# SCH_car_for_2024-01-24.net
KiCad netlist of a schematic drawn in EasyEDA
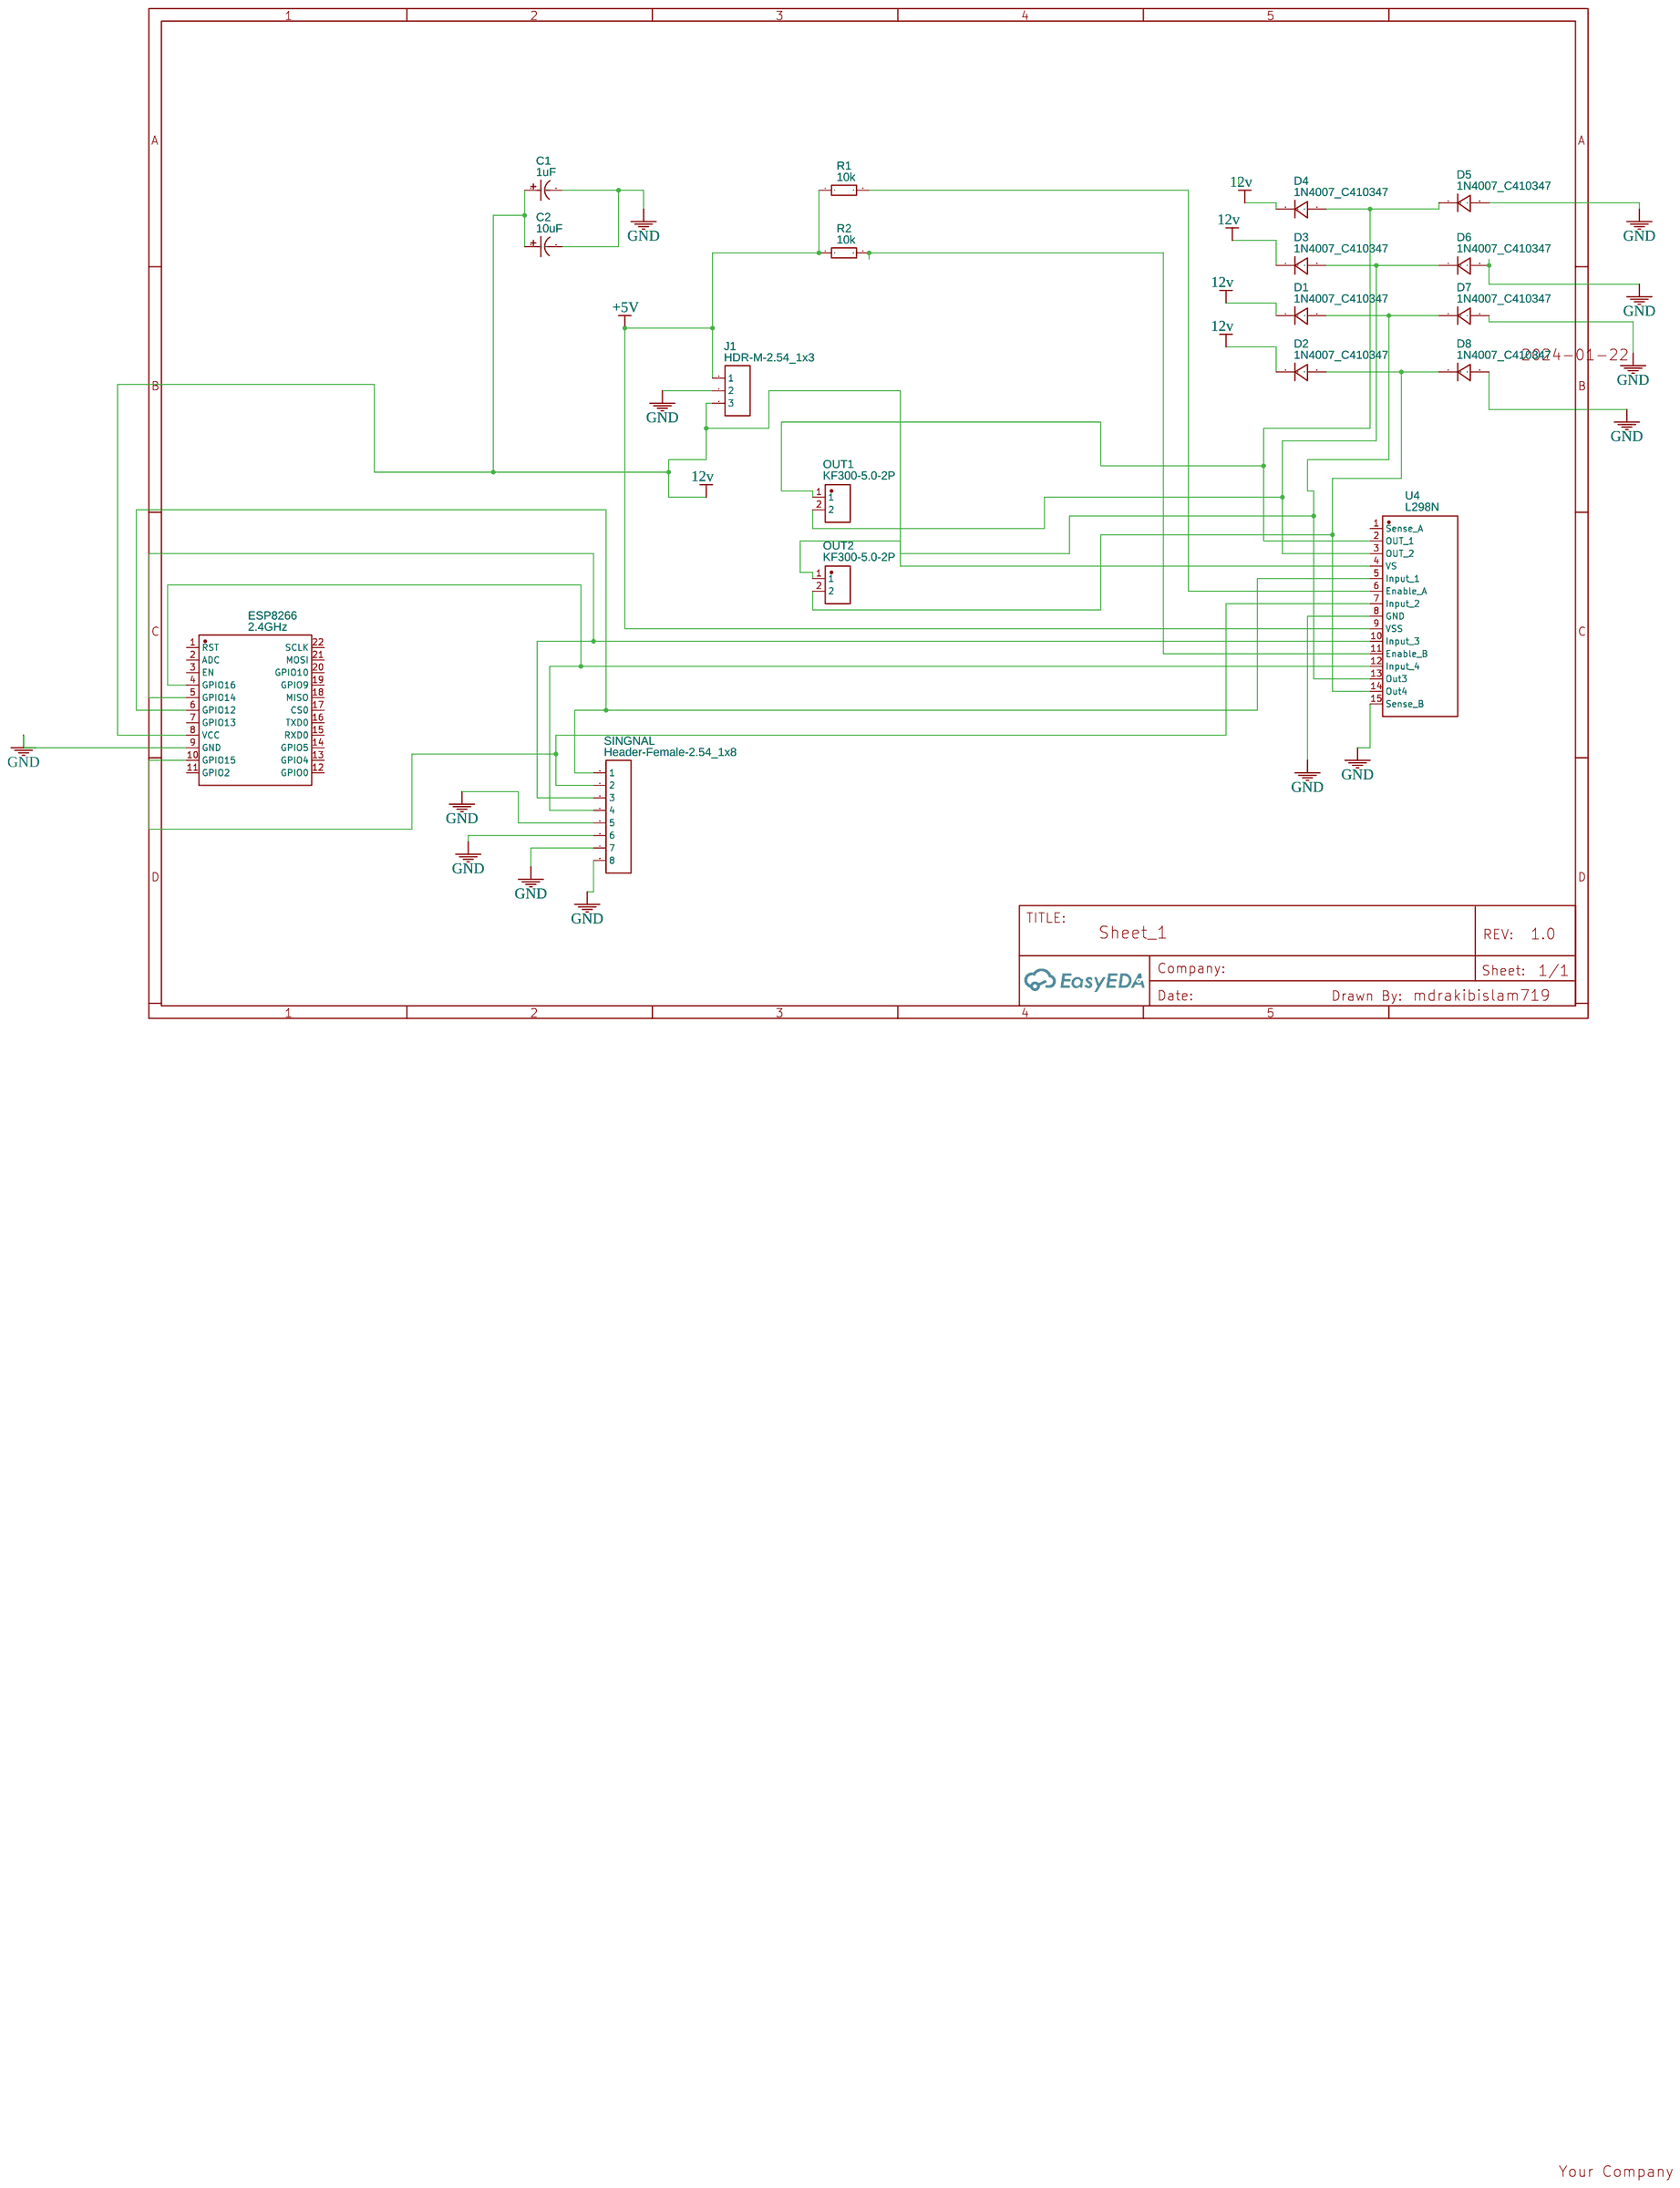
[diagram p0: Sheet_1]
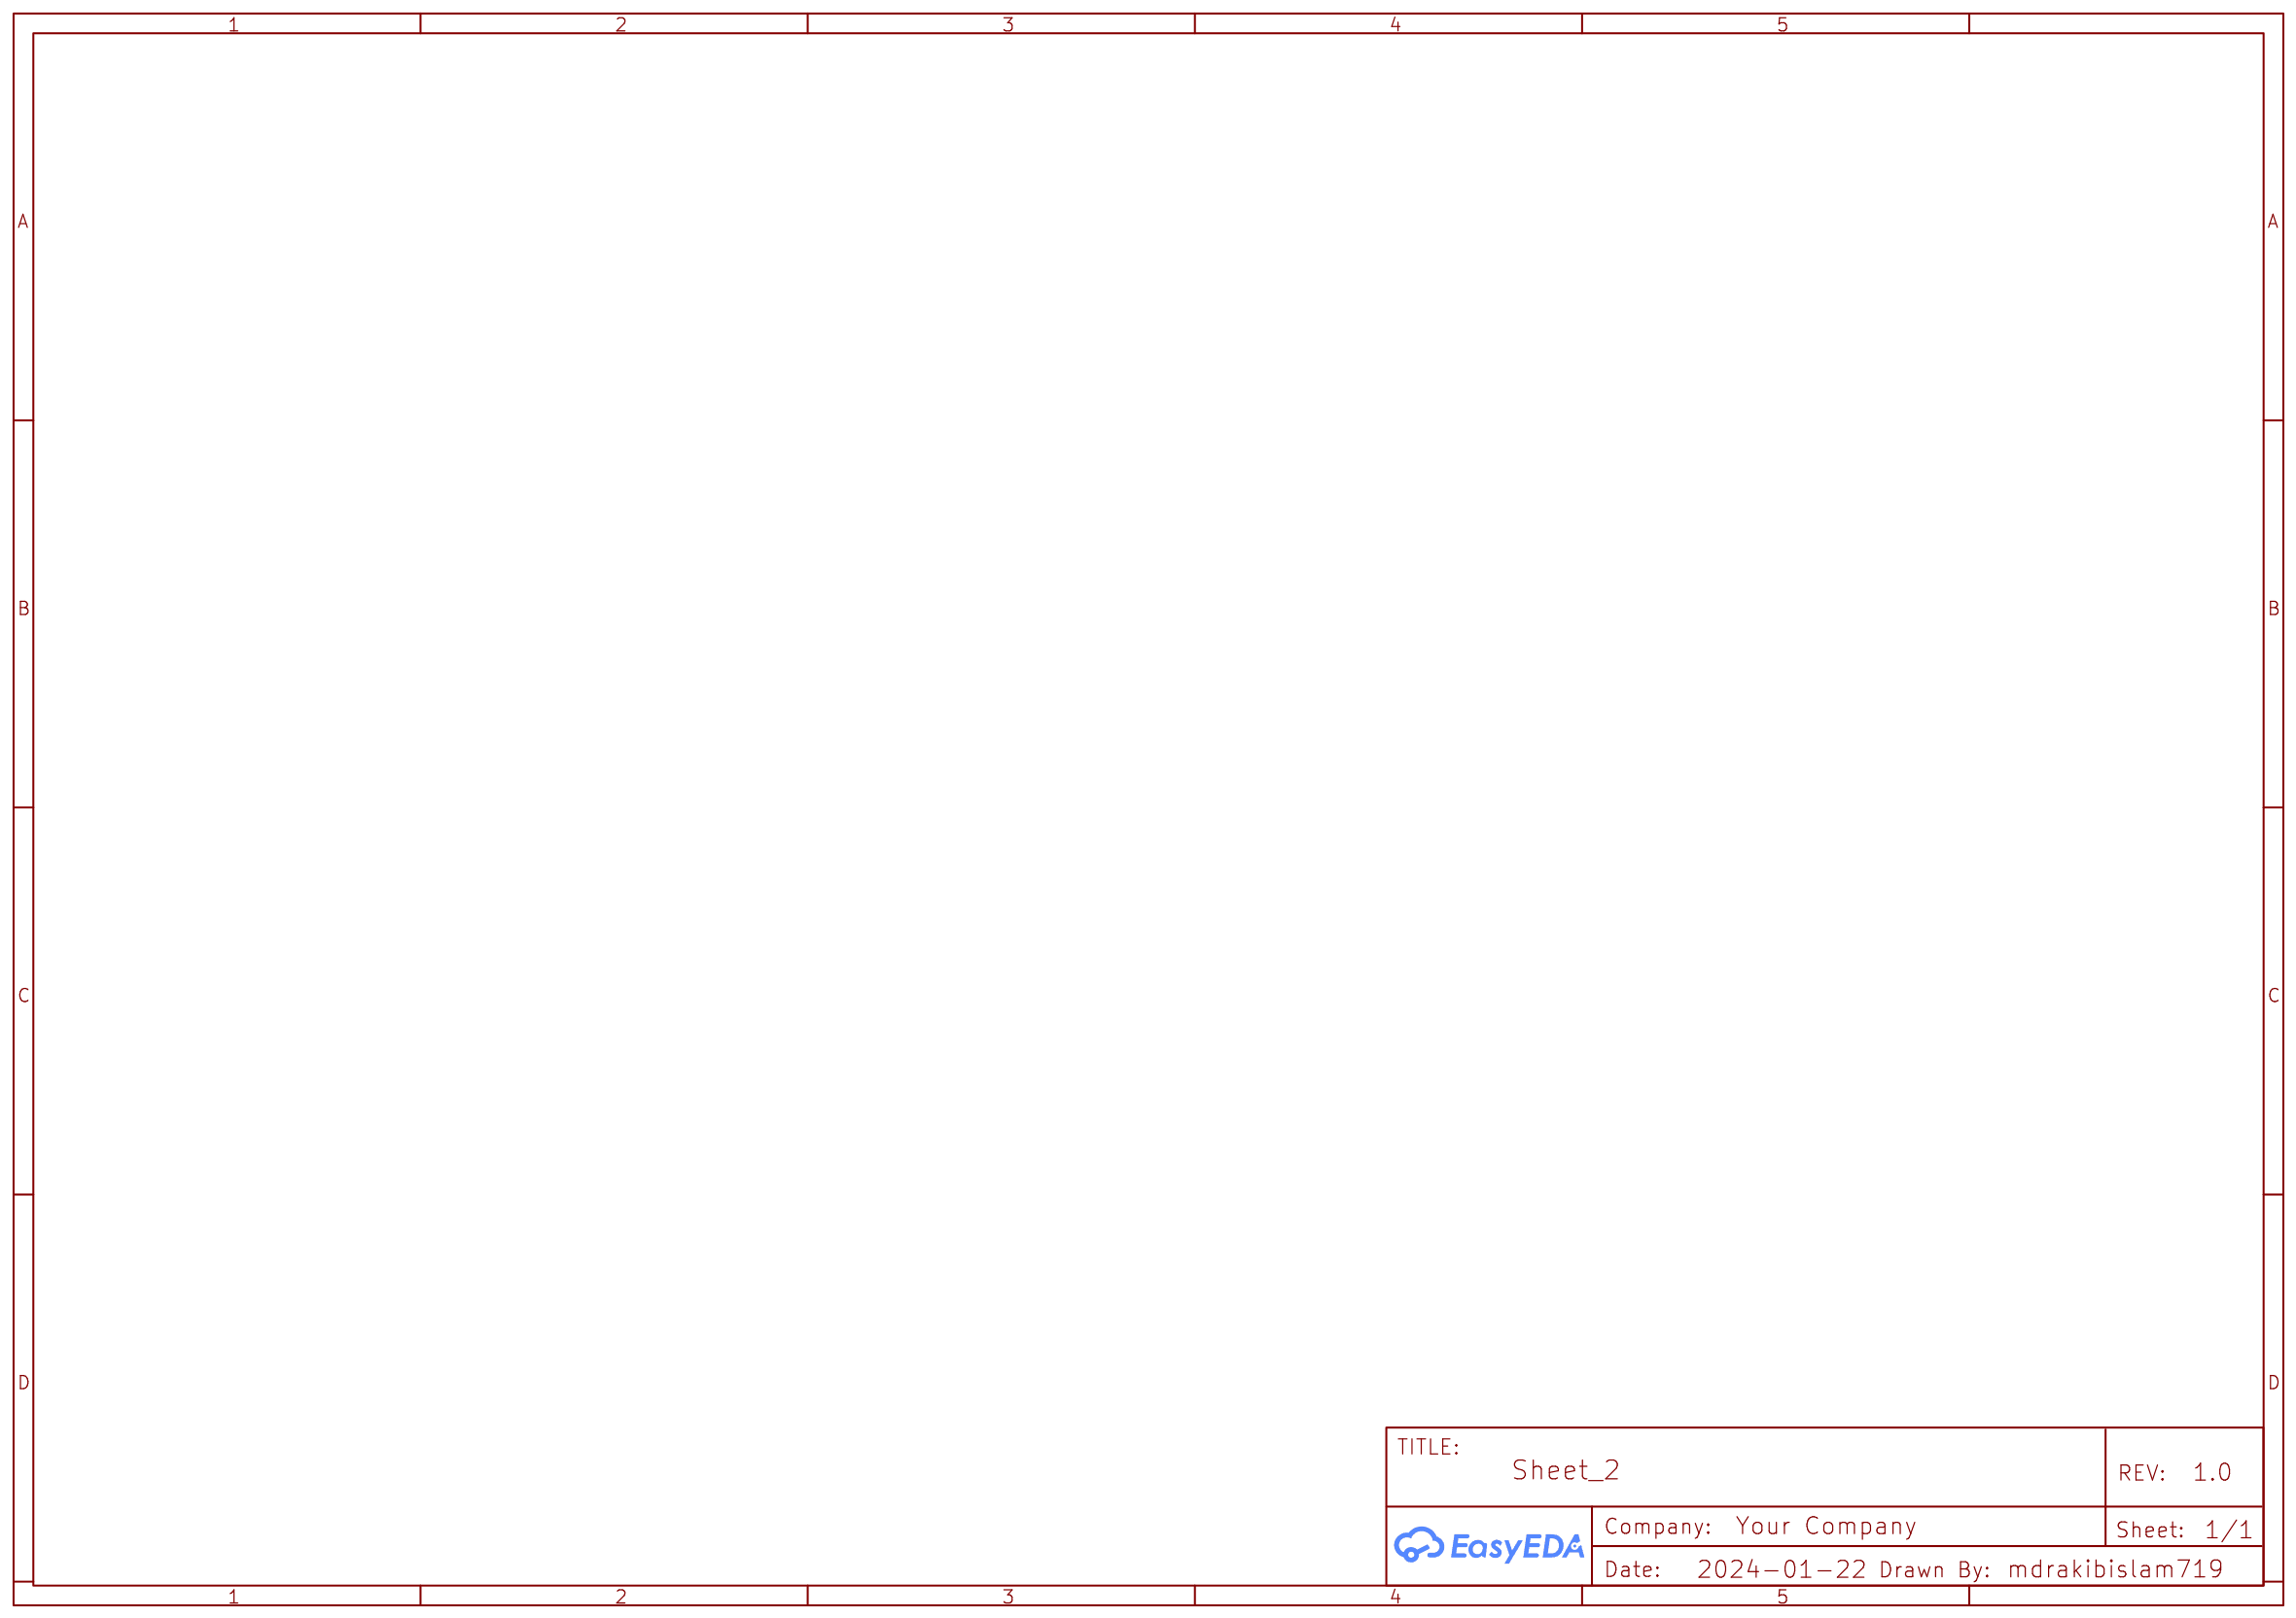
[diagram p1: Sheet_2]

(export (version "E")
  (design (tool "Eeschema 10.0.6"))
  (components
    (comp (ref "C1")
      (value "1uF")
      (fields
        (field (name "Manufacturer Part") "KF105M050C05RR0VH2FP0")
        (field (name "Manufacturer") "CX(承兴)")
      )
      (libsource (lib "") (part "1uF 50V 4*5"))
    )
    (comp (ref "C2")
      (value "10uF")
      (fields
        (field (name "Manufacturer Part") "KM106M025D11RR0VH2FP0")
        (field (name "Manufacturer") "CX(承兴)")
      )
      (libsource (lib "") (part "10uF 25V 5*11"))
    )
    (comp (ref "D1")
      (value "1N4007_C410347")
      (fields (field (name "Manufacturer Part") "1N4007-TB") (field (name "Manufacturer") "GOOD-ARK(固锝)"))
      (libsource (lib "") (part "1N4007_C410347"))
    )
    (comp (ref "D2")
      (value "1N4007_C410347")
      (fields (field (name "Manufacturer Part") "1N4007-TB") (field (name "Manufacturer") "GOOD-ARK(固锝)"))
      (libsource (lib "") (part "1N4007_C410347"))
    )
    (comp (ref "D3")
      (value "1N4007_C410347")
      (fields (field (name "Manufacturer Part") "1N4007-TB") (field (name "Manufacturer") "GOOD-ARK(固锝)"))
      (libsource (lib "") (part "1N4007_C410347"))
    )
    (comp (ref "D4")
      (value "1N4007_C410347")
      (fields (field (name "Manufacturer Part") "1N4007-TB") (field (name "Manufacturer") "GOOD-ARK(固锝)"))
      (libsource (lib "") (part "1N4007_C410347"))
    )
    (comp (ref "D5")
      (value "1N4007_C410347")
      (fields (field (name "Manufacturer Part") "1N4007-TB") (field (name "Manufacturer") "GOOD-ARK(固锝)"))
      (libsource (lib "") (part "1N4007_C410347"))
    )
    (comp (ref "D6")
      (value "1N4007_C410347")
      (fields (field (name "Manufacturer Part") "1N4007-TB") (field (name "Manufacturer") "GOOD-ARK(固锝)"))
      (libsource (lib "") (part "1N4007_C410347"))
    )
    (comp (ref "D7")
      (value "1N4007_C410347")
      (fields (field (name "Manufacturer Part") "1N4007-TB") (field (name "Manufacturer") "GOOD-ARK(固锝)"))
      (libsource (lib "") (part "1N4007_C410347"))
    )
    (comp (ref "D8")
      (value "1N4007_C410347")
      (fields (field (name "Manufacturer Part") "1N4007-TB") (field (name "Manufacturer") "GOOD-ARK(固锝)"))
      (libsource (lib "") (part "1N4007_C410347"))
    )
    (comp (ref "ESP8266")
      (value "2.4GHz")
      (fields
        (field (name "Manufacturer Part") "ESP-12F(ESP8266MOD)")
        (field (name "Manufacturer") "Ai-Thinker(安信可)")
      )
      (libsource (lib "") (part "ESP-12F(ESP8266MOD)"))
    )
    (comp (ref "J1") (value "HDR-M-2.54_1x3") (libsource (lib "") (part "HDR-M-2.54_1x3")))
    (comp (ref "OUT1")
      (value "KF300-5.0-2P")
      (fields (field (name "Manufacturer") "KEFA(科发)"))
      (libsource (lib "") (part "KF300-5.0-2P"))
    )
    (comp (ref "OUT2")
      (value "KF300-5.0-2P")
      (fields (field (name "Manufacturer") "KEFA(科发)"))
      (libsource (lib "") (part "KF300-5.0-2P"))
    )
    (comp (ref "R1")
      (value "10k")
      (fields (field (name "Manufacturer Part") "7501/2w5%"))
      (libsource (lib "") (part "750Ω"))
    )
    (comp (ref "R2")
      (value "10k")
      (fields (field (name "Manufacturer Part") "7501/2w5%"))
      (libsource (lib "") (part "750Ω"))
    )
    (comp (ref "SINGNAL")
      (value "Header-Female-2.54_1x8")
      (fields (field (name "Manufacturer Part") "2.54-1*8P母环保") (field (name "Manufacturer") "BOOMELE(博穆精密)"))
      (libsource (lib "") (part "Header-Female-2.54_1x8"))
    )
    (comp (ref "U4")
      (value "L298N")
      (fields (field (name "Manufacturer") "HGSEMI(华冠)"))
      (libsource (lib "") (part "L298N"))
    )
  )
  (nets
    (net (code "1") (name "+5V") (class "Default")
      (node (ref "J1") (pin "1") (pinfunction "1_1") (pintype "input"))
      (node (ref "R1") (pin "1") (pinfunction "1_1") (pintype "input"))
      (node (ref "R2") (pin "1") (pinfunction "1_1") (pintype "input"))
      (node (ref "U4") (pin "9") (pinfunction "VSS_9") (pintype "unspecified"))
    )
    (net (code "2") (name "12v") (class "Default")
      (node (ref "C1") (pin "1") (pinfunction "1_1") (pintype "input"))
      (node (ref "C2") (pin "1") (pinfunction "1_1") (pintype "input"))
      (node (ref "D1") (pin "1") (pinfunction "C_1") (pintype "unspecified"))
      (node (ref "D2") (pin "1") (pinfunction "C_1") (pintype "unspecified"))
      (node (ref "D3") (pin "1") (pinfunction "C_1") (pintype "unspecified"))
      (node (ref "D4") (pin "1") (pinfunction "C_1") (pintype "unspecified"))
      (node (ref "ESP8266") (pin "8") (pinfunction "VCC_8") (pintype "unspecified"))
      (node (ref "J1") (pin "3") (pinfunction "3_3") (pintype "input"))
      (node (ref "U4") (pin "4") (pinfunction "VS_4") (pintype "unspecified"))
    )
    (net (code "3") (name "GND") (class "Default")
      (node (ref "C1") (pin "2") (pinfunction "2_2") (pintype "input"))
      (node (ref "C2") (pin "2") (pinfunction "2_2") (pintype "input"))
      (node (ref "D5") (pin "2") (pinfunction "A_2") (pintype "unspecified"))
      (node (ref "D6") (pin "2") (pinfunction "A_2") (pintype "unspecified"))
      (node (ref "D7") (pin "2") (pinfunction "A_2") (pintype "unspecified"))
      (node (ref "D8") (pin "2") (pinfunction "A_2") (pintype "unspecified"))
      (node (ref "ESP8266") (pin "9") (pinfunction "GND_9") (pintype "unspecified"))
      (node (ref "J1") (pin "2") (pinfunction "2_2") (pintype "input"))
      (node (ref "SINGNAL") (pin "5") (pinfunction "5_5") (pintype "input"))
      (node (ref "SINGNAL") (pin "6") (pinfunction "6_6") (pintype "input"))
      (node (ref "SINGNAL") (pin "7") (pinfunction "7_7") (pintype "input"))
      (node (ref "SINGNAL") (pin "8") (pinfunction "8_8") (pintype "input"))
      (node (ref "U4") (pin "15") (pinfunction "Sense_B_15") (pintype "unspecified"))
      (node (ref "U4") (pin "8") (pinfunction "GND_8") (pintype "unspecified"))
    )
    (net (code "4") (name "Net-(D1-A)") (class "Default")
      (node (ref "D1") (pin "2") (pinfunction "A_2") (pintype "unspecified"))
      (node (ref "D7") (pin "1") (pinfunction "C_1") (pintype "unspecified"))
      (node (ref "OUT2") (pin "1") (pinfunction "1_1") (pintype "unspecified"))
      (node (ref "U4") (pin "13") (pinfunction "Out3_13") (pintype "unspecified"))
    )
    (net (code "5") (name "Net-(D2-A)") (class "Default")
      (node (ref "D2") (pin "2") (pinfunction "A_2") (pintype "unspecified"))
      (node (ref "D8") (pin "1") (pinfunction "C_1") (pintype "unspecified"))
      (node (ref "OUT2") (pin "2") (pinfunction "2_2") (pintype "unspecified"))
      (node (ref "U4") (pin "14") (pinfunction "Out4_14") (pintype "unspecified"))
    )
    (net (code "6") (name "Net-(D3-A)") (class "Default")
      (node (ref "D3") (pin "2") (pinfunction "A_2") (pintype "unspecified"))
      (node (ref "D6") (pin "1") (pinfunction "C_1") (pintype "unspecified"))
      (node (ref "OUT1") (pin "2") (pinfunction "2_2") (pintype "unspecified"))
      (node (ref "U4") (pin "3") (pinfunction "OUT_2_3") (pintype "unspecified"))
    )
    (net (code "7") (name "Net-(D4-A)") (class "Default")
      (node (ref "D4") (pin "2") (pinfunction "A_2") (pintype "unspecified"))
      (node (ref "D5") (pin "1") (pinfunction "C_1") (pintype "unspecified"))
      (node (ref "OUT1") (pin "1") (pinfunction "1_1") (pintype "unspecified"))
      (node (ref "U4") (pin "2") (pinfunction "OUT_1_2") (pintype "unspecified"))
    )
    (net (code "8") (name "Net-(ESP8266-GPIO12)") (class "Default")
      (node (ref "ESP8266") (pin "6") (pinfunction "GPIO12_6") (pintype "unspecified"))
      (node (ref "SINGNAL") (pin "1") (pinfunction "1_1") (pintype "input"))
      (node (ref "U4") (pin "5") (pinfunction "Input_1_5") (pintype "unspecified"))
    )
    (net (code "9") (name "Net-(ESP8266-GPIO14)") (class "Default")
      (node (ref "ESP8266") (pin "5") (pinfunction "GPIO14_5") (pintype "unspecified"))
      (node (ref "SINGNAL") (pin "3") (pinfunction "3_3") (pintype "input"))
      (node (ref "U4") (pin "10") (pinfunction "Input_3_10") (pintype "unspecified"))
    )
    (net (code "10") (name "Net-(ESP8266-GPIO15)") (class "Default")
      (node (ref "ESP8266") (pin "10") (pinfunction "GPIO15_10") (pintype "unspecified"))
      (node (ref "SINGNAL") (pin "2") (pinfunction "2_2") (pintype "input"))
      (node (ref "U4") (pin "7") (pinfunction "Input_2_7") (pintype "unspecified"))
    )
    (net (code "11") (name "Net-(ESP8266-GPIO16)") (class "Default")
      (node (ref "ESP8266") (pin "4") (pinfunction "GPIO16_4") (pintype "unspecified"))
      (node (ref "SINGNAL") (pin "4") (pinfunction "4_4") (pintype "input"))
      (node (ref "U4") (pin "12") (pinfunction "Input_4_12") (pintype "unspecified"))
    )
    (net (code "12") (name "Net-(U4-Enable_A)") (class "Default")
      (node (ref "R1") (pin "2") (pinfunction "2_2") (pintype "input"))
      (node (ref "U4") (pin "6") (pinfunction "Enable_A_6") (pintype "unspecified"))
    )
    (net (code "13") (name "Net-(U4-Enable_B)") (class "Default")
      (node (ref "R2") (pin "2") (pinfunction "2_2") (pintype "input"))
      (node (ref "U4") (pin "11") (pinfunction "Enable_B_11") (pintype "unspecified"))
    )
    (net (code "14") (name "unconnected-(ESP8266-ADC-Pad2)") (class "Default")
      (node (ref "ESP8266") (pin "2") (pinfunction "ADC_2") (pintype "unspecified"))
    )
    (net (code "15") (name "unconnected-(ESP8266-CS0-Pad17)") (class "Default")
      (node (ref "ESP8266") (pin "17") (pinfunction "CS0_17") (pintype "unspecified"))
    )
    (net (code "16") (name "unconnected-(ESP8266-EN-Pad3)") (class "Default")
      (node (ref "ESP8266") (pin "3") (pinfunction "EN_3") (pintype "unspecified"))
    )
    (net (code "17") (name "unconnected-(ESP8266-GPIO0-Pad12)") (class "Default")
      (node (ref "ESP8266") (pin "12") (pinfunction "GPIO0_12") (pintype "unspecified"))
    )
    (net (code "18") (name "unconnected-(ESP8266-GPIO2-Pad11)") (class "Default")
      (node (ref "ESP8266") (pin "11") (pinfunction "GPIO2_11") (pintype "unspecified"))
    )
    (net (code "19") (name "unconnected-(ESP8266-GPIO4-Pad13)") (class "Default")
      (node (ref "ESP8266") (pin "13") (pinfunction "GPIO4_13") (pintype "unspecified"))
    )
    (net (code "20") (name "unconnected-(ESP8266-GPIO5-Pad14)") (class "Default")
      (node (ref "ESP8266") (pin "14") (pinfunction "GPIO5_14") (pintype "unspecified"))
    )
    (net (code "21") (name "unconnected-(ESP8266-GPIO9-Pad19)") (class "Default")
      (node (ref "ESP8266") (pin "19") (pinfunction "GPIO9_19") (pintype "unspecified"))
    )
    (net (code "22") (name "unconnected-(ESP8266-GPIO10-Pad20)") (class "Default")
      (node (ref "ESP8266") (pin "20") (pinfunction "GPIO10_20") (pintype "unspecified"))
    )
    (net (code "23") (name "unconnected-(ESP8266-GPIO13-Pad7)") (class "Default")
      (node (ref "ESP8266") (pin "7") (pinfunction "GPIO13_7") (pintype "unspecified"))
    )
    (net (code "24") (name "unconnected-(ESP8266-MISO-Pad18)") (class "Default")
      (node (ref "ESP8266") (pin "18") (pinfunction "MISO_18") (pintype "unspecified"))
    )
    (net (code "25") (name "unconnected-(ESP8266-MOSI-Pad21)") (class "Default")
      (node (ref "ESP8266") (pin "21") (pinfunction "MOSI_21") (pintype "unspecified"))
    )
    (net (code "26") (name "unconnected-(ESP8266-RST-Pad1)") (class "Default")
      (node (ref "ESP8266") (pin "1") (pinfunction "RST_1") (pintype "unspecified"))
    )
    (net (code "27") (name "unconnected-(ESP8266-RXD0-Pad15)") (class "Default")
      (node (ref "ESP8266") (pin "15") (pinfunction "RXD0_15") (pintype "unspecified"))
    )
    (net (code "28") (name "unconnected-(ESP8266-SCLK-Pad22)") (class "Default")
      (node (ref "ESP8266") (pin "22") (pinfunction "SCLK_22") (pintype "unspecified"))
    )
    (net (code "29") (name "unconnected-(ESP8266-TXD0-Pad16)") (class "Default")
      (node (ref "ESP8266") (pin "16") (pinfunction "TXD0_16") (pintype "unspecified"))
    )
    (net (code "30") (name "unconnected-(U4-Sense_A-Pad1)") (class "Default")
      (node (ref "U4") (pin "1") (pinfunction "Sense_A_1") (pintype "unspecified"))
    )
  )
)
